# sheet.net
KiCad netlist of a schematic drawn in Altium Designer
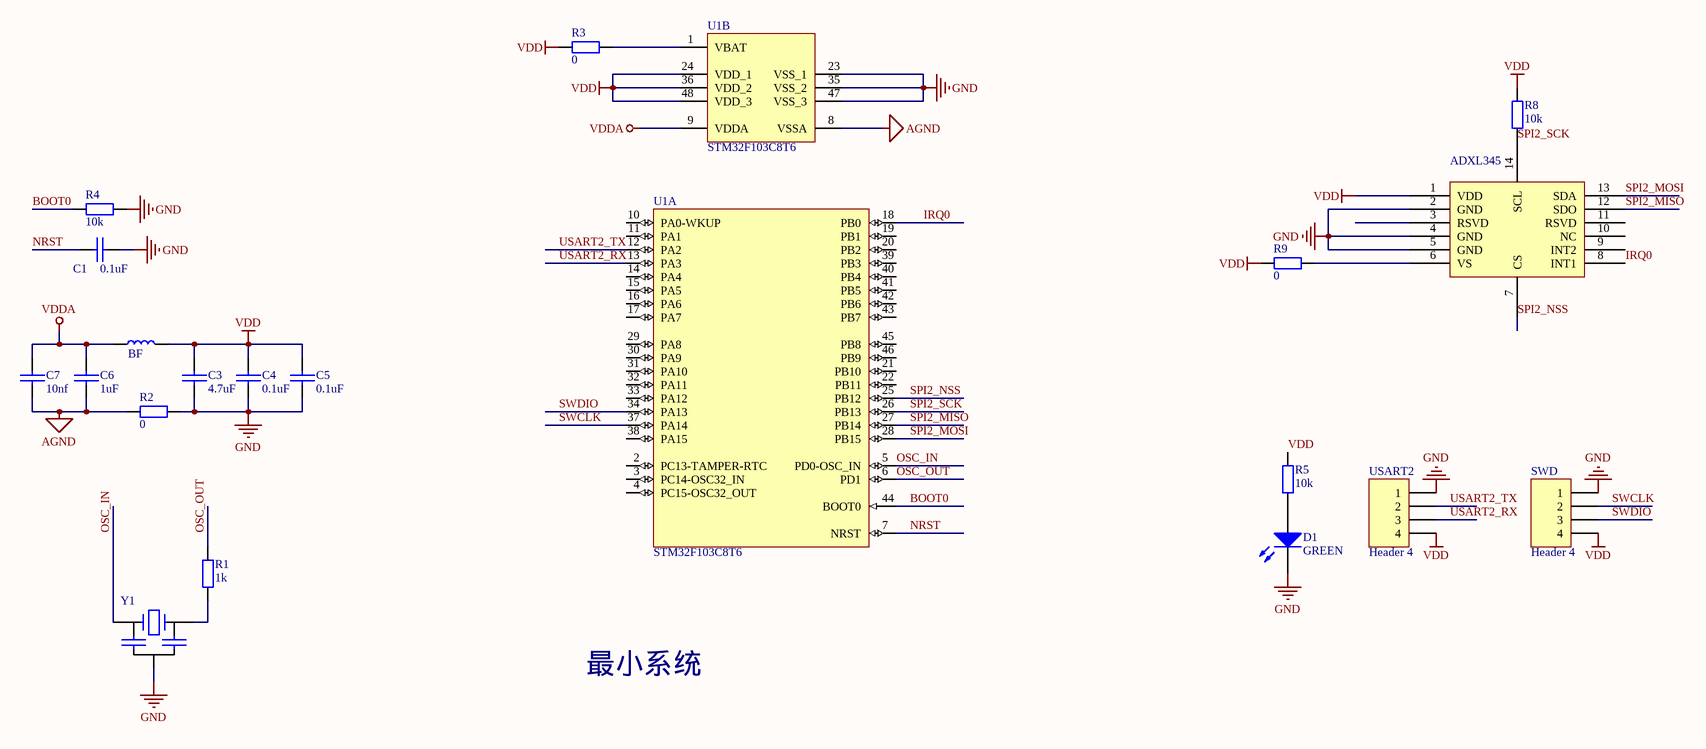
[diagram p0: sheet.SchDoc]

(export (version "E")
  (design (tool "Eeschema 10.0.6"))
  (components
    (comp (ref "ADXL345")
      (value "ADXL345")
      (footprint "ADXL345")
      (libsource (lib "ADIS345SHEETLIB") (part "ADXL345"))
    )
    (comp (ref "BF")
      (value "BF")
      (footprint "R1608[0603]")
      (description "磁珠")
      (libsource (lib "SkyWorks2") (part "BF"))
    )
    (comp (ref "C1")
      (value "0.1uF")
      (footprint "C1608[0603]N")
      (description "贴片无极性电容")
      (fields (field (name "Comment") "cap smd"))
      (libsource (lib "SkyWorks") (part "CAP"))
    )
    (comp (ref "C3")
      (value "4.7uF")
      (footprint "C1608[0603]N")
      (description "贴片无极性电容")
      (fields (field (name "Comment") "cap smd"))
      (libsource (lib "SkyWorks2") (part "CAP"))
    )
    (comp (ref "C4")
      (value "0.1uF")
      (footprint "C1608[0603]N")
      (description "贴片无极性电容")
      (fields (field (name "Comment") "cap smd"))
      (libsource (lib "SkyWorks2") (part "CAP"))
    )
    (comp (ref "C5")
      (value "0.1uF")
      (footprint "C1608[0603]N")
      (description "贴片无极性电容")
      (fields (field (name "Comment") "cap smd"))
      (libsource (lib "SkyWorks2") (part "CAP"))
    )
    (comp (ref "C6")
      (value "1uF")
      (footprint "C1608[0603]N")
      (description "贴片无极性电容")
      (fields (field (name "Comment") "cap smd"))
      (libsource (lib "SkyWorks2") (part "CAP"))
    )
    (comp (ref "C7")
      (value "10nf")
      (footprint "C1608[0603]N")
      (description "贴片无极性电容")
      (fields (field (name "Comment") "cap smd"))
      (libsource (lib "SkyWorks2") (part "CAP"))
    )
    (comp (ref "D1")
      (value "GREEN")
      (footprint "D1608[0603]")
      (description "蓝色 LED")
      (fields (field (name "Comment") "LED") (field (name "PUBLISHER") "Altium Limited"))
      (libsource (lib "SkyWorks") (part "LED"))
    )
    (comp (ref "R1")
      (value "1k")
      (footprint "R1608[0603]")
      (fields (field (name "Comment") "RES1"))
      (libsource (lib "SkyWorks2") (part "RES1"))
    )
    (comp (ref "R2")
      (value "0")
      (footprint "R1608[0603]")
      (fields (field (name "Comment") "RES1"))
      (libsource (lib "SkyWorks2") (part "RES1"))
    )
    (comp (ref "R3")
      (value "0")
      (footprint "1608[0603]")
      (fields (field (name "Comment") "RES1"))
      (libsource (lib "SkyWorks2") (part "RES1"))
    )
    (comp (ref "R4")
      (value "10k")
      (footprint "R1608[0603]")
      (fields (field (name "Comment") "RES1"))
      (libsource (lib "SkyWorks2") (part "RES1"))
    )
    (comp (ref "R5")
      (value "10k")
      (footprint "R1608[0603]")
      (fields (field (name "Comment") "RES1"))
      (libsource (lib "SkyWorks2") (part "RES1"))
    )
    (comp (ref "R8")
      (value "10k")
      (footprint "R1608[0603]")
      (fields (field (name "Comment") "RES1"))
      (libsource (lib "SkyWorks") (part "RES1"))
    )
    (comp (ref "R9")
      (value "0")
      (footprint "R1608[0603]")
      (fields (field (name "Comment") "RES1"))
      (libsource (lib "SkyWorks") (part "RES1"))
    )
    (comp (ref "SWD")
      (value "Header 4")
      (footprint "HDR1X4")
      (description "Header, 4-Pin")
      (fields (field (name "PUBLISHER") "Altium Limited"))
      (libsource (lib "Miscellaneous Connectors") (part "Header 4"))
    )
    (comp (ref "U1")
      (value "STM32F103C8T6")
      (footprint "STMicroelectronics STM32 F1:LQFP48_N")
      (libsource (lib "STMicroelectronics STM32 F1") (part "STM32F103C8T6"))
    )
    (comp (ref "USART2")
      (value "Header 4")
      (footprint "HDR1X4")
      (description "Header, 4-Pin")
      (fields (field (name "PUBLISHER") "Altium Limited"))
      (libsource (lib "Miscellaneous Connectors") (part "Header 4"))
    )
    (comp (ref "Y1")
      (value "CSTCE8M00G52")
      (footprint "Crystal_C")
      (description "Crystal_8M")
      (libsource (lib "SkyWorks2") (part "CRYSTAL_C"))
    )
  )
  (nets
    (net (code "1") (name "/BOOT0") (class "Default")
      (node (ref "R4") (pin "2") (pinfunction "2_2") (pintype "passive"))
      (node (ref "U1") (pin "44") (pinfunction "BOOT0_44") (pintype "input"))
    )
    (net (code "2") (name "/IRQ0") (class "Default")
      (node (ref "ADXL345") (pin "8") (pinfunction "INT1_8") (pintype "passive"))
      (node (ref "U1") (pin "18") (pinfunction "PB0_18") (pintype "bidirectional"))
    )
    (net (code "3") (name "/NRST") (class "Default")
      (node (ref "C1") (pin "2") (pinfunction "2_2") (pintype "passive"))
      (node (ref "U1") (pin "7") (pinfunction "NRST_7") (pintype "bidirectional"))
    )
    (net (code "4") (name "/OSC_IN") (class "Default")
      (node (ref "U1") (pin "5") (pinfunction "PD0-OSC_IN_5") (pintype "bidirectional"))
      (node (ref "Y1") (pin "1") (pinfunction "1_1") (pintype "passive"))
    )
    (net (code "5") (name "/OSC_OUT") (class "Default")
      (node (ref "R1") (pin "2") (pinfunction "2_2") (pintype "passive"))
      (node (ref "U1") (pin "6") (pinfunction "PD1_6") (pintype "bidirectional"))
    )
    (net (code "6") (name "/SPI2_MISO") (class "Default")
      (node (ref "ADXL345") (pin "12") (pinfunction "SDO_12") (pintype "passive"))
      (node (ref "U1") (pin "27") (pinfunction "PB14_27") (pintype "bidirectional"))
    )
    (net (code "7") (name "/SPI2_MOSI") (class "Default")
      (node (ref "ADXL345") (pin "13") (pinfunction "SDA_13") (pintype "passive"))
      (node (ref "U1") (pin "28") (pinfunction "PB15_28") (pintype "bidirectional"))
    )
    (net (code "8") (name "/SPI2_NSS") (class "Default")
      (node (ref "ADXL345") (pin "7") (pinfunction "CS_7") (pintype "passive"))
      (node (ref "U1") (pin "25") (pinfunction "PB12_25") (pintype "bidirectional"))
    )
    (net (code "9") (name "/SPI2_SCK") (class "Default")
      (node (ref "ADXL345") (pin "14") (pinfunction "SCL_14") (pintype "passive"))
      (node (ref "R8") (pin "1") (pinfunction "1_1") (pintype "passive"))
      (node (ref "U1") (pin "26") (pinfunction "PB13_26") (pintype "bidirectional"))
    )
    (net (code "10") (name "/SWCLK") (class "Default")
      (node (ref "SWD") (pin "2") (pinfunction "2_2") (pintype "passive"))
      (node (ref "U1") (pin "37") (pinfunction "PA14_37") (pintype "bidirectional"))
    )
    (net (code "11") (name "/SWDIO") (class "Default")
      (node (ref "SWD") (pin "3") (pinfunction "3_3") (pintype "passive"))
      (node (ref "U1") (pin "34") (pinfunction "PA13_34") (pintype "bidirectional"))
    )
    (net (code "12") (name "/USART2_RX") (class "Default")
      (node (ref "U1") (pin "13") (pinfunction "PA3_13") (pintype "bidirectional"))
      (node (ref "USART2") (pin "3") (pinfunction "3_3") (pintype "passive"))
    )
    (net (code "13") (name "/USART2_TX") (class "Default")
      (node (ref "U1") (pin "12") (pinfunction "PA2_12") (pintype "bidirectional"))
      (node (ref "USART2") (pin "2") (pinfunction "2_2") (pintype "passive"))
    )
    (net (code "14") (name "AGND") (class "Default")
      (node (ref "C6") (pin "2") (pinfunction "2_2") (pintype "passive"))
      (node (ref "C7") (pin "2") (pinfunction "2_2") (pintype "passive"))
      (node (ref "R2") (pin "1") (pinfunction "1_1") (pintype "passive"))
      (node (ref "U1") (pin "8") (pinfunction "VSSA_8") (pintype "power_in"))
    )
    (net (code "15") (name "GND") (class "Default")
      (node (ref "ADXL345") (pin "2") (pinfunction "GND_2") (pintype "passive"))
      (node (ref "ADXL345") (pin "4") (pinfunction "GND_4") (pintype "passive"))
      (node (ref "ADXL345") (pin "5") (pinfunction "GND_5") (pintype "passive"))
      (node (ref "C1") (pin "1") (pinfunction "1_1") (pintype "passive"))
      (node (ref "C3") (pin "2") (pinfunction "2_2") (pintype "passive"))
      (node (ref "C4") (pin "2") (pinfunction "2_2") (pintype "passive"))
      (node (ref "C5") (pin "2") (pinfunction "2_2") (pintype "passive"))
      (node (ref "D1") (pin "2") (pinfunction "K_2") (pintype "passive"))
      (node (ref "R2") (pin "2") (pinfunction "2_2") (pintype "passive"))
      (node (ref "R4") (pin "1") (pinfunction "1_1") (pintype "passive"))
      (node (ref "SWD") (pin "1") (pinfunction "1_1") (pintype "passive"))
      (node (ref "U1") (pin "23") (pinfunction "VSS_1_23") (pintype "power_in"))
      (node (ref "U1") (pin "35") (pinfunction "VSS_2_35") (pintype "power_in"))
      (node (ref "U1") (pin "47") (pinfunction "VSS_3_47") (pintype "power_in"))
      (node (ref "USART2") (pin "1") (pinfunction "1_1") (pintype "passive"))
      (node (ref "Y1") (pin "2") (pinfunction "GND_2") (pintype "passive"))
    )
    (net (code "16") (name "Net-(ADXL345-VS)") (class "Default")
      (node (ref "ADXL345") (pin "6") (pinfunction "VS_6") (pintype "passive"))
      (node (ref "R9") (pin "2") (pinfunction "2_2") (pintype "passive"))
    )
    (net (code "17") (name "Net-(D1-A)") (class "Default")
      (node (ref "D1") (pin "1") (pinfunction "A_1") (pintype "passive"))
      (node (ref "R5") (pin "1") (pinfunction "1_1") (pintype "passive"))
    )
    (net (code "18") (name "Net-(R1-Pad1)") (class "Default")
      (node (ref "R1") (pin "1") (pinfunction "1_1") (pintype "passive"))
      (node (ref "Y1") (pin "3") (pinfunction "3_3") (pintype "passive"))
    )
    (net (code "19") (name "Net-(U1B-VBAT)") (class "Default")
      (node (ref "R3") (pin "2") (pinfunction "2_2") (pintype "passive"))
      (node (ref "U1") (pin "1") (pinfunction "VBAT_1") (pintype "power_in"))
    )
    (net (code "20") (name "VDD") (class "Default")
      (node (ref "ADXL345") (pin "1") (pinfunction "VDD_1") (pintype "passive"))
      (node (ref "BF") (pin "2") (pinfunction "2_2") (pintype "passive"))
      (node (ref "C3") (pin "1") (pinfunction "1_1") (pintype "passive"))
      (node (ref "C4") (pin "1") (pinfunction "1_1") (pintype "passive"))
      (node (ref "C5") (pin "1") (pinfunction "1_1") (pintype "passive"))
      (node (ref "R3") (pin "1") (pinfunction "1_1") (pintype "passive"))
      (node (ref "R5") (pin "2") (pinfunction "2_2") (pintype "passive"))
      (node (ref "R8") (pin "2") (pinfunction "2_2") (pintype "passive"))
      (node (ref "R9") (pin "1") (pinfunction "1_1") (pintype "passive"))
      (node (ref "SWD") (pin "4") (pinfunction "4_4") (pintype "passive"))
      (node (ref "U1") (pin "24") (pinfunction "VDD_1_24") (pintype "power_in"))
      (node (ref "U1") (pin "36") (pinfunction "VDD_2_36") (pintype "power_in"))
      (node (ref "U1") (pin "48") (pinfunction "VDD_3_48") (pintype "power_in"))
      (node (ref "USART2") (pin "4") (pinfunction "4_4") (pintype "passive"))
    )
    (net (code "21") (name "VDDA") (class "Default")
      (node (ref "BF") (pin "1") (pinfunction "1_1") (pintype "passive"))
      (node (ref "C6") (pin "1") (pinfunction "1_1") (pintype "passive"))
      (node (ref "C7") (pin "1") (pinfunction "1_1") (pintype "passive"))
      (node (ref "U1") (pin "9") (pinfunction "VDDA_9") (pintype "power_in"))
    )
    (net (code "22") (name "unconnected-(ADXL345-INT2-Pad9)") (class "Default")
      (node (ref "ADXL345") (pin "9") (pinfunction "INT2_9") (pintype "passive"))
    )
    (net (code "23") (name "unconnected-(ADXL345-NC-Pad10)") (class "Default")
      (node (ref "ADXL345") (pin "10") (pinfunction "NC_10") (pintype "passive"))
    )
    (net (code "24") (name "unconnected-(ADXL345-RSVD-Pad3)") (class "Default")
      (node (ref "ADXL345") (pin "3") (pinfunction "RSVD_3") (pintype "passive"))
    )
    (net (code "25") (name "unconnected-(ADXL345-RSVD-Pad11)") (class "Default")
      (node (ref "ADXL345") (pin "11") (pinfunction "RSVD_11") (pintype "passive"))
    )
    (net (code "26") (name "unconnected-(U1A-PA0-WKUP-Pad10)") (class "Default")
      (node (ref "U1") (pin "10") (pinfunction "PA0-WKUP_10") (pintype "bidirectional"))
    )
    (net (code "27") (name "unconnected-(U1A-PA1-Pad11)") (class "Default")
      (node (ref "U1") (pin "11") (pinfunction "PA1_11") (pintype "bidirectional"))
    )
    (net (code "28") (name "unconnected-(U1A-PA4-Pad14)") (class "Default")
      (node (ref "U1") (pin "14") (pinfunction "PA4_14") (pintype "bidirectional"))
    )
    (net (code "29") (name "unconnected-(U1A-PA5-Pad15)") (class "Default")
      (node (ref "U1") (pin "15") (pinfunction "PA5_15") (pintype "bidirectional"))
    )
    (net (code "30") (name "unconnected-(U1A-PA6-Pad16)") (class "Default")
      (node (ref "U1") (pin "16") (pinfunction "PA6_16") (pintype "bidirectional"))
    )
    (net (code "31") (name "unconnected-(U1A-PA7-Pad17)") (class "Default")
      (node (ref "U1") (pin "17") (pinfunction "PA7_17") (pintype "bidirectional"))
    )
    (net (code "32") (name "unconnected-(U1A-PA8-Pad29)") (class "Default")
      (node (ref "U1") (pin "29") (pinfunction "PA8_29") (pintype "bidirectional"))
    )
    (net (code "33") (name "unconnected-(U1A-PA9-Pad30)") (class "Default")
      (node (ref "U1") (pin "30") (pinfunction "PA9_30") (pintype "bidirectional"))
    )
    (net (code "34") (name "unconnected-(U1A-PA10-Pad31)") (class "Default")
      (node (ref "U1") (pin "31") (pinfunction "PA10_31") (pintype "bidirectional"))
    )
    (net (code "35") (name "unconnected-(U1A-PA11-Pad32)") (class "Default")
      (node (ref "U1") (pin "32") (pinfunction "PA11_32") (pintype "bidirectional"))
    )
    (net (code "36") (name "unconnected-(U1A-PA12-Pad33)") (class "Default")
      (node (ref "U1") (pin "33") (pinfunction "PA12_33") (pintype "bidirectional"))
    )
    (net (code "37") (name "unconnected-(U1A-PA15-Pad38)") (class "Default")
      (node (ref "U1") (pin "38") (pinfunction "PA15_38") (pintype "bidirectional"))
    )
    (net (code "38") (name "unconnected-(U1A-PB1-Pad19)") (class "Default")
      (node (ref "U1") (pin "19") (pinfunction "PB1_19") (pintype "bidirectional"))
    )
    (net (code "39") (name "unconnected-(U1A-PB2-Pad20)") (class "Default")
      (node (ref "U1") (pin "20") (pinfunction "PB2_20") (pintype "bidirectional"))
    )
    (net (code "40") (name "unconnected-(U1A-PB3-Pad39)") (class "Default")
      (node (ref "U1") (pin "39") (pinfunction "PB3_39") (pintype "bidirectional"))
    )
    (net (code "41") (name "unconnected-(U1A-PB4-Pad40)") (class "Default")
      (node (ref "U1") (pin "40") (pinfunction "PB4_40") (pintype "bidirectional"))
    )
    (net (code "42") (name "unconnected-(U1A-PB5-Pad41)") (class "Default")
      (node (ref "U1") (pin "41") (pinfunction "PB5_41") (pintype "bidirectional"))
    )
    (net (code "43") (name "unconnected-(U1A-PB6-Pad42)") (class "Default")
      (node (ref "U1") (pin "42") (pinfunction "PB6_42") (pintype "bidirectional"))
    )
    (net (code "44") (name "unconnected-(U1A-PB7-Pad43)") (class "Default")
      (node (ref "U1") (pin "43") (pinfunction "PB7_43") (pintype "bidirectional"))
    )
    (net (code "45") (name "unconnected-(U1A-PB8-Pad45)") (class "Default")
      (node (ref "U1") (pin "45") (pinfunction "PB8_45") (pintype "bidirectional"))
    )
    (net (code "46") (name "unconnected-(U1A-PB9-Pad46)") (class "Default")
      (node (ref "U1") (pin "46") (pinfunction "PB9_46") (pintype "bidirectional"))
    )
    (net (code "47") (name "unconnected-(U1A-PB10-Pad21)") (class "Default")
      (node (ref "U1") (pin "21") (pinfunction "PB10_21") (pintype "bidirectional"))
    )
    (net (code "48") (name "unconnected-(U1A-PB11-Pad22)") (class "Default")
      (node (ref "U1") (pin "22") (pinfunction "PB11_22") (pintype "bidirectional"))
    )
    (net (code "49") (name "unconnected-(U1A-PC13-TAMPER-RTC-Pad2)") (class "Default")
      (node (ref "U1") (pin "2") (pinfunction "PC13-TAMPER-RTC_2") (pintype "bidirectional"))
    )
    (net (code "50") (name "unconnected-(U1A-PC14-OSC32_IN-Pad3)") (class "Default")
      (node (ref "U1") (pin "3") (pinfunction "PC14-OSC32_IN_3") (pintype "bidirectional"))
    )
    (net (code "51") (name "unconnected-(U1A-PC15-OSC32_OUT-Pad4)") (class "Default")
      (node (ref "U1") (pin "4") (pinfunction "PC15-OSC32_OUT_4") (pintype "bidirectional"))
    )
  )
)
